# Single-Thermocouple-Shield.net
KiCad netlist of a schematic drawn in EAGLE
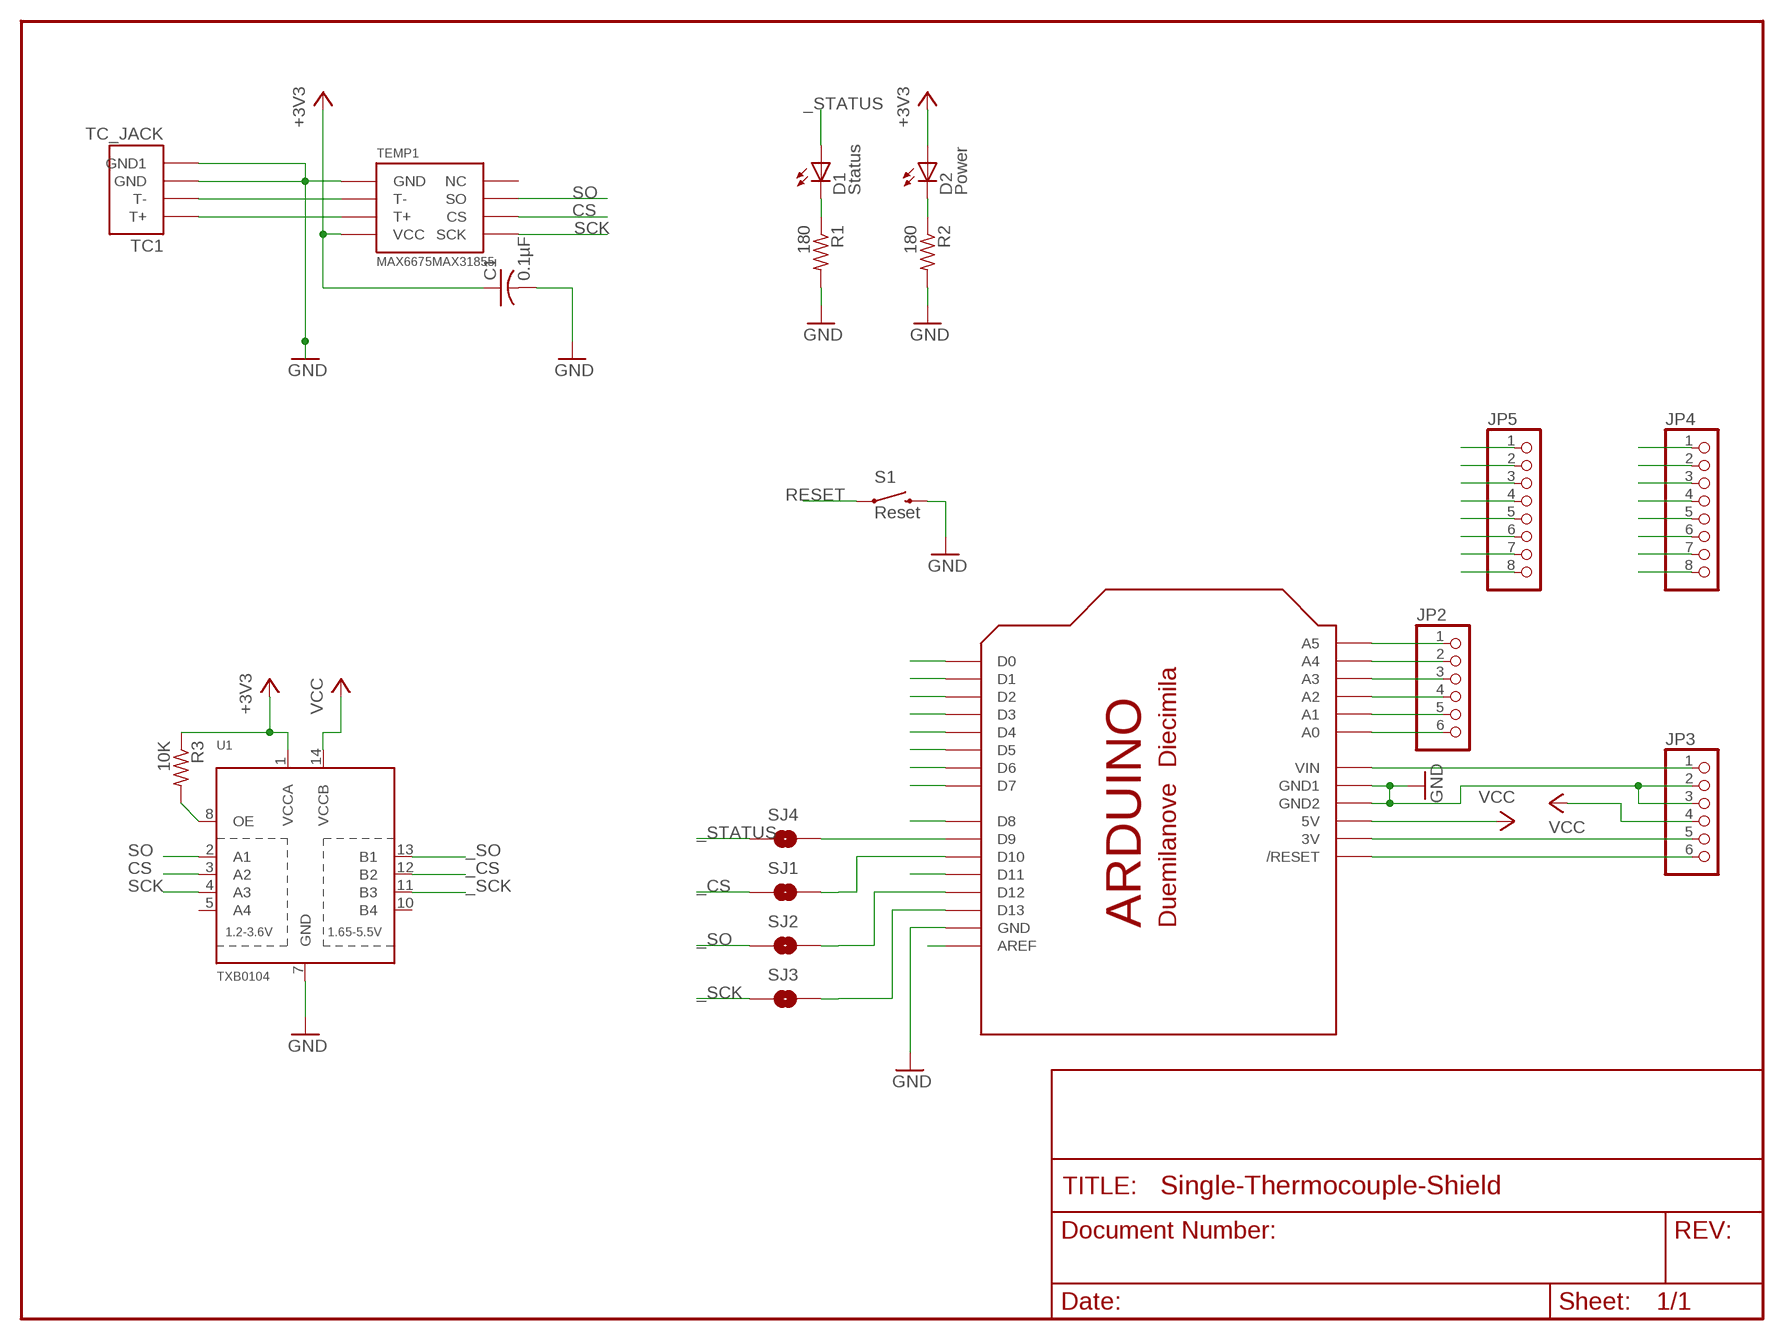
[diagram p0: schematic, sheet 1]

(export (version "E")
  (design (tool "Eeschema 10.0.6"))
  (components
    (comp (ref "C1")
      (value "0.1µF")
      (footprint "eagle-import:C0603")
      (libsource (lib "eagle-import") (part "C-USC0603"))
    )
    (comp (ref "D1")
      (value "Status")
      (footprint "eagle-import:CHIPLED_0805")
      (libsource (lib "eagle-import") (part "LEDCHIPLED_0805"))
    )
    (comp (ref "D2")
      (value "Power")
      (footprint "eagle-import:CHIPLED_0805")
      (libsource (lib "eagle-import") (part "LEDCHIPLED_0805"))
    )
    (comp (ref "JP2")
      (value "PINHD-1X6CB")
      (footprint "eagle-import:1X06-CLEANBIG")
      (libsource (lib "eagle-import") (part "PINHD-1X6CB"))
    )
    (comp (ref "JP3")
      (value "PINHD-1X6CB")
      (footprint "eagle-import:1X06-CLEANBIG")
      (libsource (lib "eagle-import") (part "PINHD-1X6CB"))
    )
    (comp (ref "JP4")
      (value "PINHD-1X8CLEANBIG")
      (footprint "eagle-import:1X08-CLEANBIG")
      (libsource (lib "eagle-import") (part "PINHD-1X8CLEANBIG"))
    )
    (comp (ref "JP5")
      (value "PINHD-1X8CLEANBIG")
      (footprint "eagle-import:1X08-CLEANBIG")
      (libsource (lib "eagle-import") (part "PINHD-1X8CLEANBIG"))
    )
    (comp (ref "R1")
      (value "180")
      (footprint "eagle-import:R0603")
      (libsource (lib "eagle-import") (part "R-US_R0603"))
    )
    (comp (ref "R2")
      (value "180")
      (footprint "eagle-import:R0603")
      (libsource (lib "eagle-import") (part "R-US_R0603"))
    )
    (comp (ref "R3")
      (value "10K")
      (footprint "eagle-import:R0603")
      (libsource (lib "eagle-import") (part "R-US_R0603"))
    )
    (comp (ref "S1")
      (value "Reset")
      (footprint "eagle-import:TACTILE_SWITCH_SMD")
      (libsource (lib "eagle-import") (part "SWITCH-MOMENTARY-2SMD"))
    )
    (comp (ref "SJ1")
      (value "SOLDERJUMPERTRACE")
      (footprint "eagle-import:SJ_2S-TRACE")
      (libsource (lib "eagle-import") (part "SOLDERJUMPERTRACE"))
    )
    (comp (ref "SJ2")
      (value "SOLDERJUMPERTRACE")
      (footprint "eagle-import:SJ_2S-TRACE")
      (libsource (lib "eagle-import") (part "SOLDERJUMPERTRACE"))
    )
    (comp (ref "SJ3")
      (value "SOLDERJUMPERTRACE")
      (footprint "eagle-import:SJ_2S-TRACE")
      (libsource (lib "eagle-import") (part "SOLDERJUMPERTRACE"))
    )
    (comp (ref "SJ4")
      (value "SOLDERJUMPERTRACE")
      (footprint "eagle-import:SJ_2S-TRACE")
      (libsource (lib "eagle-import") (part "SOLDERJUMPERTRACE"))
    )
    (comp (ref "TC1")
      (value "TC_JACK")
      (footprint "eagle-import:TC_JACK")
      (libsource (lib "eagle-import") (part "TC_JACK"))
    )
    (comp (ref "TEMP1")
      (value "MAX6675MAX31855")
      (footprint "eagle-import:SOIC-8")
      (libsource (lib "eagle-import") (part "MAX6675MAX31855"))
    )
    (comp (ref "U$3")
      (value "ARDUINOUNO")
      (footprint "eagle-import:ARDUINO")
      (libsource (lib "eagle-import") (part "ARDUINOUNO"))
    )
    (comp (ref "U1")
      (value "TXB0104")
      (footprint "eagle-import:TSSOP14")
      (libsource (lib "eagle-import") (part "TXB0104PWR"))
    )
  )
  (nets
    (net (code "1") (name "+3V3") (class "Default")
      (node (ref "C1") (pin "1") (pinfunction "1_1") (pintype "passive"))
      (node (ref "D2") (pin "A") (pinfunction "A_A") (pintype "passive"))
      (node (ref "JP3") (pin "5") (pinfunction "5_5") (pintype "passive"))
      (node (ref "R3") (pin "1") (pinfunction "1_1") (pintype "passive"))
      (node (ref "TEMP1") (pin "VCC") (pinfunction "VCC_VCC") (pintype "bidirectional"))
      (node (ref "U$3") (pin "3V") (pinfunction "3V_3V") (pintype "power_in"))
      (node (ref "U1") (pin "1") (pinfunction "VCCA_1") (pintype "bidirectional"))
    )
    (net (code "2") (name "/AREF") (class "Default")
      (node (ref "JP4") (pin "8") (pinfunction "8_8") (pintype "passive"))
      (node (ref "U$3") (pin "AREF") (pinfunction "AREF_AREF") (pintype "bidirectional"))
    )
    (net (code "3") (name "/CS") (class "Default")
      (node (ref "TEMP1") (pin "CS") (pinfunction "CS_CS") (pintype "bidirectional"))
      (node (ref "U1") (pin "3") (pinfunction "A2_3") (pintype "bidirectional"))
    )
    (net (code "4") (name "/D0") (class "Default")
      (node (ref "JP5") (pin "1") (pinfunction "1_1") (pintype "passive"))
      (node (ref "U$3") (pin "D0") (pinfunction "D0_D0") (pintype "bidirectional"))
    )
    (net (code "5") (name "/D1") (class "Default")
      (node (ref "JP5") (pin "2") (pinfunction "2_2") (pintype "passive"))
      (node (ref "U$3") (pin "D1") (pinfunction "D1_D1") (pintype "bidirectional"))
    )
    (net (code "6") (name "/D2") (class "Default")
      (node (ref "JP5") (pin "3") (pinfunction "3_3") (pintype "passive"))
      (node (ref "U$3") (pin "D2") (pinfunction "D2_D2") (pintype "bidirectional"))
    )
    (net (code "7") (name "/D3") (class "Default")
      (node (ref "JP5") (pin "4") (pinfunction "4_4") (pintype "passive"))
      (node (ref "U$3") (pin "D3") (pinfunction "D3_D3") (pintype "bidirectional"))
    )
    (net (code "8") (name "/D4") (class "Default")
      (node (ref "JP5") (pin "5") (pinfunction "5_5") (pintype "passive"))
      (node (ref "U$3") (pin "D4") (pinfunction "D4_D4") (pintype "bidirectional"))
    )
    (net (code "9") (name "/D5") (class "Default")
      (node (ref "JP5") (pin "6") (pinfunction "6_6") (pintype "passive"))
      (node (ref "U$3") (pin "D5") (pinfunction "D5_D5") (pintype "bidirectional"))
    )
    (net (code "10") (name "/D6") (class "Default")
      (node (ref "JP5") (pin "7") (pinfunction "7_7") (pintype "passive"))
      (node (ref "U$3") (pin "D6") (pinfunction "D6_D6") (pintype "bidirectional"))
    )
    (net (code "11") (name "/D7") (class "Default")
      (node (ref "JP5") (pin "8") (pinfunction "8_8") (pintype "passive"))
      (node (ref "U$3") (pin "D7") (pinfunction "D7_D7") (pintype "bidirectional"))
    )
    (net (code "12") (name "/D8") (class "Default")
      (node (ref "JP4") (pin "1") (pinfunction "1_1") (pintype "passive"))
      (node (ref "U$3") (pin "D8") (pinfunction "D8_D8") (pintype "bidirectional"))
    )
    (net (code "13") (name "/D9") (class "Default")
      (node (ref "JP4") (pin "2") (pinfunction "2_2") (pintype "passive"))
      (node (ref "SJ4") (pin "2") (pinfunction "2_2") (pintype "passive"))
      (node (ref "U$3") (pin "D9") (pinfunction "D9_D9") (pintype "bidirectional"))
    )
    (net (code "14") (name "/D10") (class "Default")
      (node (ref "JP4") (pin "3") (pinfunction "3_3") (pintype "passive"))
      (node (ref "SJ1") (pin "2") (pinfunction "2_2") (pintype "passive"))
      (node (ref "U$3") (pin "D10") (pinfunction "D10_D10") (pintype "bidirectional"))
    )
    (net (code "15") (name "/D11") (class "Default")
      (node (ref "JP4") (pin "4") (pinfunction "4_4") (pintype "passive"))
      (node (ref "U$3") (pin "D11") (pinfunction "D11_D11") (pintype "bidirectional"))
    )
    (net (code "16") (name "/D12") (class "Default")
      (node (ref "JP4") (pin "5") (pinfunction "5_5") (pintype "passive"))
      (node (ref "SJ2") (pin "2") (pinfunction "2_2") (pintype "passive"))
      (node (ref "U$3") (pin "D12") (pinfunction "D12_D12") (pintype "bidirectional"))
    )
    (net (code "17") (name "/D13") (class "Default")
      (node (ref "JP4") (pin "6") (pinfunction "6_6") (pintype "passive"))
      (node (ref "SJ3") (pin "2") (pinfunction "2_2") (pintype "passive"))
      (node (ref "U$3") (pin "D13") (pinfunction "D13_D13") (pintype "bidirectional"))
    )
    (net (code "18") (name "/RESET") (class "Default")
      (node (ref "JP3") (pin "6") (pinfunction "6_6") (pintype "passive"))
      (node (ref "S1") (pin "1") (pinfunction "1_1") (pintype "passive"))
      (node (ref "U$3") (pin "RESET") (pinfunction "/RESET_RESET") (pintype "bidirectional"))
    )
    (net (code "19") (name "/SCK") (class "Default")
      (node (ref "TEMP1") (pin "SCK") (pinfunction "SCK_SCK") (pintype "bidirectional"))
      (node (ref "U1") (pin "4") (pinfunction "A3_4") (pintype "bidirectional"))
    )
    (net (code "20") (name "/SO") (class "Default")
      (node (ref "TEMP1") (pin "SO") (pinfunction "SO_SO") (pintype "bidirectional"))
      (node (ref "U1") (pin "2") (pinfunction "A1_2") (pintype "bidirectional"))
    )
    (net (code "21") (name "/_CS") (class "Default")
      (node (ref "SJ1") (pin "1") (pinfunction "1_1") (pintype "passive"))
      (node (ref "U1") (pin "12") (pinfunction "B2_12") (pintype "bidirectional"))
    )
    (net (code "22") (name "/_SCK") (class "Default")
      (node (ref "SJ3") (pin "1") (pinfunction "1_1") (pintype "passive"))
      (node (ref "U1") (pin "11") (pinfunction "B3_11") (pintype "bidirectional"))
    )
    (net (code "23") (name "/_SO") (class "Default")
      (node (ref "SJ2") (pin "1") (pinfunction "1_1") (pintype "passive"))
      (node (ref "U1") (pin "13") (pinfunction "B1_13") (pintype "bidirectional"))
    )
    (net (code "24") (name "/_STATUS") (class "Default")
      (node (ref "D1") (pin "A") (pinfunction "A_A") (pintype "passive"))
      (node (ref "SJ4") (pin "1") (pinfunction "1_1") (pintype "passive"))
    )
    (net (code "25") (name "GND") (class "Default")
      (node (ref "C1") (pin "2") (pinfunction "2_2") (pintype "passive"))
      (node (ref "JP3") (pin "2") (pinfunction "2_2") (pintype "passive"))
      (node (ref "JP3") (pin "3") (pinfunction "3_3") (pintype "passive"))
      (node (ref "JP4") (pin "7") (pinfunction "7_7") (pintype "passive"))
      (node (ref "R1") (pin "2") (pinfunction "2_2") (pintype "passive"))
      (node (ref "R2") (pin "2") (pinfunction "2_2") (pintype "passive"))
      (node (ref "S1") (pin "3") (pinfunction "2_3") (pintype "passive"))
      (node (ref "TC1") (pin "P$1") (pinfunction "GND_P$1") (pintype "bidirectional"))
      (node (ref "TC1") (pin "P$2") (pinfunction "GND1_P$2") (pintype "bidirectional"))
      (node (ref "TEMP1") (pin "GND") (pinfunction "GND_GND") (pintype "bidirectional"))
      (node (ref "U$3") (pin "GND") (pinfunction "GND_GND") (pintype "power_in"))
      (node (ref "U$3") (pin "GND1") (pinfunction "GND1_GND1") (pintype "power_in"))
      (node (ref "U$3") (pin "GND2") (pinfunction "GND2_GND2") (pintype "power_in"))
      (node (ref "U1") (pin "7") (pinfunction "GND_7") (pintype "bidirectional"))
    )
    (net (code "26") (name "Net-(D1-PadC)") (class "Default")
      (node (ref "D1") (pin "C") (pinfunction "C_C") (pintype "passive"))
      (node (ref "R1") (pin "1") (pinfunction "1_1") (pintype "passive"))
    )
    (net (code "27") (name "Net-(D2-PadC)") (class "Default")
      (node (ref "D2") (pin "C") (pinfunction "C_C") (pintype "passive"))
      (node (ref "R2") (pin "1") (pinfunction "1_1") (pintype "passive"))
    )
    (net (code "28") (name "Net-(JP2-Pad1)") (class "Default")
      (node (ref "JP2") (pin "1") (pinfunction "1_1") (pintype "passive"))
      (node (ref "U$3") (pin "A5") (pinfunction "A5_A5") (pintype "bidirectional"))
    )
    (net (code "29") (name "Net-(JP2-Pad2)") (class "Default")
      (node (ref "JP2") (pin "2") (pinfunction "2_2") (pintype "passive"))
      (node (ref "U$3") (pin "A4") (pinfunction "A4_A4") (pintype "bidirectional"))
    )
    (net (code "30") (name "Net-(JP2-Pad3)") (class "Default")
      (node (ref "JP2") (pin "3") (pinfunction "3_3") (pintype "passive"))
      (node (ref "U$3") (pin "A3") (pinfunction "A3_A3") (pintype "bidirectional"))
    )
    (net (code "31") (name "Net-(JP2-Pad4)") (class "Default")
      (node (ref "JP2") (pin "4") (pinfunction "4_4") (pintype "passive"))
      (node (ref "U$3") (pin "A2") (pinfunction "A2_A2") (pintype "bidirectional"))
    )
    (net (code "32") (name "Net-(JP2-Pad5)") (class "Default")
      (node (ref "JP2") (pin "5") (pinfunction "5_5") (pintype "passive"))
      (node (ref "U$3") (pin "A1") (pinfunction "A1_A1") (pintype "bidirectional"))
    )
    (net (code "33") (name "Net-(JP2-Pad6)") (class "Default")
      (node (ref "JP2") (pin "6") (pinfunction "6_6") (pintype "passive"))
      (node (ref "U$3") (pin "A0") (pinfunction "A0_A0") (pintype "bidirectional"))
    )
    (net (code "34") (name "Net-(JP3-Pad1)") (class "Default")
      (node (ref "JP3") (pin "1") (pinfunction "1_1") (pintype "passive"))
      (node (ref "U$3") (pin "VIN") (pinfunction "VIN_VIN") (pintype "power_in"))
    )
    (net (code "35") (name "Net-(TC1-PadT+)") (class "Default")
      (node (ref "TC1") (pin "T+") (pinfunction "T+_T+") (pintype "bidirectional"))
      (node (ref "TEMP1") (pin "T+") (pinfunction "T+_T+") (pintype "bidirectional"))
    )
    (net (code "36") (name "Net-(TC1-PadT-)") (class "Default")
      (node (ref "TC1") (pin "T-") (pinfunction "T-_T-") (pintype "bidirectional"))
      (node (ref "TEMP1") (pin "T-") (pinfunction "T-_T-") (pintype "bidirectional"))
    )
    (net (code "37") (name "Net-(U1-OE)") (class "Default")
      (node (ref "R3") (pin "2") (pinfunction "2_2") (pintype "passive"))
      (node (ref "U1") (pin "8") (pinfunction "OE_8") (pintype "bidirectional"))
    )
    (net (code "38") (name "VCC") (class "Default")
      (node (ref "JP3") (pin "4") (pinfunction "4_4") (pintype "passive"))
      (node (ref "U$3") (pin "5V") (pinfunction "5V_5V") (pintype "power_in"))
      (node (ref "U1") (pin "14") (pinfunction "VCCB_14") (pintype "bidirectional"))
    )
    (net (code "39") (name "unconnected-(TEMP1-PadNC)") (class "Default")
      (node (ref "TEMP1") (pin "NC") (pinfunction "NC_NC") (pintype "no_connect"))
    )
    (net (code "40") (name "unconnected-(U1-A4-Pad5)") (class "Default")
      (node (ref "U1") (pin "5") (pinfunction "A4_5") (pintype "bidirectional"))
    )
    (net (code "41") (name "unconnected-(U1-B4-Pad10)") (class "Default")
      (node (ref "U1") (pin "10") (pinfunction "B4_10") (pintype "bidirectional"))
    )
  )
)
